# FR5969_BME280_v2_0_2.net
KiCad netlist of a schematic drawn in EAGLE
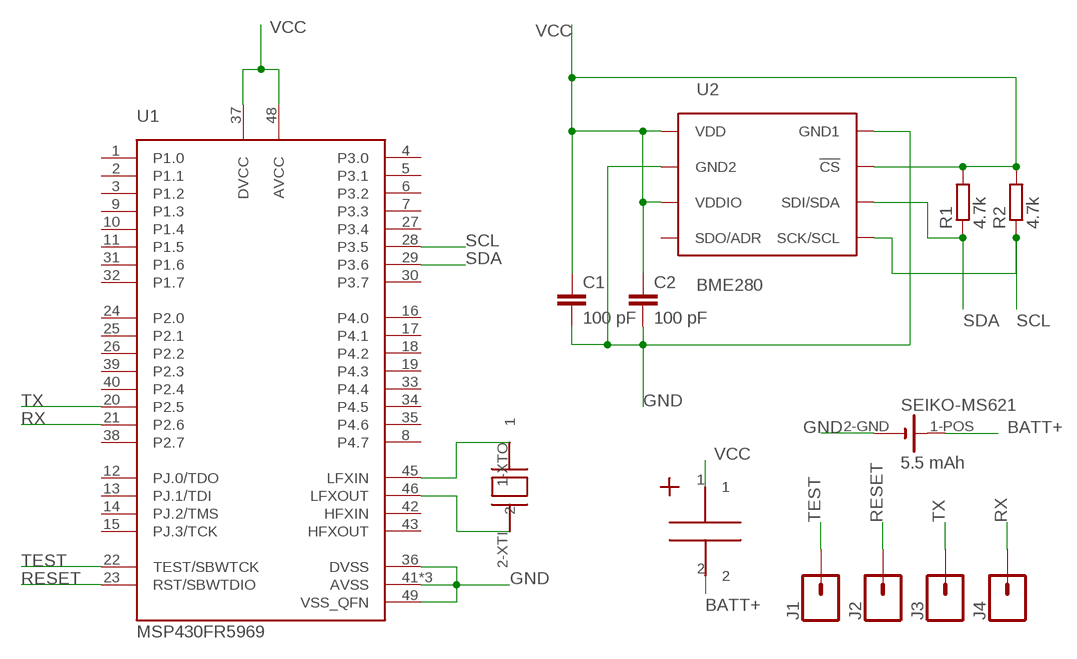
[diagram p0: schematic, sheet 1]

(export (version "E")
  (design (tool "Eeschema 10.0.6"))
  (components
    (comp (ref "C1")
      (value "100 pF")
      (footprint "eagle-import:C0201")
      (libsource (lib "eagle-import") (part "C-EUC0201"))
    )
    (comp (ref "C2")
      (value "100 pF")
      (footprint "eagle-import:C0201")
      (libsource (lib "eagle-import") (part "C-EUC0201"))
    )
    (comp (ref "J1")
      (value "CONN_01")
      (footprint "eagle-import:1X01")
      (libsource (lib "eagle-import") (part "CONN_01"))
    )
    (comp (ref "J2")
      (value "CONN_01")
      (footprint "eagle-import:1X01")
      (libsource (lib "eagle-import") (part "CONN_01"))
    )
    (comp (ref "J3")
      (value "CONN_01")
      (footprint "eagle-import:1X01")
      (libsource (lib "eagle-import") (part "CONN_01"))
    )
    (comp (ref "J4")
      (value "CONN_01")
      (footprint "eagle-import:1X01")
      (libsource (lib "eagle-import") (part "CONN_01"))
    )
    (comp (ref "R1")
      (value "4.7k")
      (footprint "eagle-import:R0201")
      (libsource (lib "eagle-import") (part "R-EU_R0201"))
    )
    (comp (ref "R2")
      (value "4.7k")
      (footprint "eagle-import:R0201")
      (libsource (lib "eagle-import") (part "R-EU_R0201"))
    )
    (comp (ref "SEIKO-MS621")
      (value "5.5 mAh")
      (footprint "eagle-import:SEIKO_MICRO")
      (libsource (lib "eagle-import") (part "SEIKO-MS621"))
    )
    (comp (ref "U$1")
      (value "CPX3225")
      (footprint "eagle-import:CPX3225_CHIP-CAP")
      (libsource (lib "eagle-import") (part "CPX3225"))
    )
    (comp (ref "U$2")
      (value "ABS06")
      (footprint "eagle-import:2.0X1.0RTC")
      (libsource (lib "eagle-import") (part "ABS06"))
    )
    (comp (ref "U1")
      (value "MSP430FR5969")
      (footprint "eagle-import:S-PVQFN-N48")
      (libsource (lib "eagle-import") (part "MSP430FR5969"))
    )
    (comp (ref "U2")
      (value "BME280")
      (footprint "eagle-import:BME280_LGA")
      (libsource (lib "eagle-import") (part "BME280"))
    )
  )
  (nets
    (net (code "1") (name "/BATT+") (class "Default")
      (node (ref "SEIKO-MS621") (pin "1-POS") (pinfunction "+_1-POS") (pintype "passive"))
      (node (ref "U$1") (pin "2") (pinfunction "2_2") (pintype "bidirectional"))
    )
    (net (code "2") (name "/GND") (class "Default")
      (node (ref "C1") (pin "2") (pinfunction "2_2") (pintype "passive"))
      (node (ref "C2") (pin "2") (pinfunction "2_2") (pintype "passive"))
      (node (ref "SEIKO-MS621") (pin "2-GND") (pinfunction "-_2-GND") (pintype "passive"))
      (node (ref "U1") (pin "36") (pinfunction "DVSS_36") (pintype "bidirectional"))
      (node (ref "U1") (pin "41") (pinfunction "AVSS_41") (pintype "bidirectional"))
      (node (ref "U1") (pin "44") (pinfunction "AVSS_44") (pintype "bidirectional"))
      (node (ref "U1") (pin "47") (pinfunction "AVSS_47") (pintype "bidirectional"))
      (node (ref "U1") (pin "49") (pinfunction "VSS_QFN_49") (pintype "bidirectional"))
      (node (ref "U2") (pin "P$1") (pinfunction "GND1_P$1") (pintype "bidirectional"))
      (node (ref "U2") (pin "P$7") (pinfunction "GND2_P$7") (pintype "bidirectional"))
    )
    (net (code "3") (name "/RESET") (class "Default")
      (node (ref "J2") (pin "1") (pinfunction "1_1") (pintype "passive"))
      (node (ref "U1") (pin "23") (pinfunction "RST/SBWTDIO_23") (pintype "bidirectional"))
    )
    (net (code "4") (name "/RX") (class "Default")
      (node (ref "J4") (pin "1") (pinfunction "1_1") (pintype "passive"))
      (node (ref "U1") (pin "21") (pinfunction "P2.6_21") (pintype "bidirectional"))
    )
    (net (code "5") (name "/SCL") (class "Default")
      (node (ref "R2") (pin "1") (pinfunction "1_1") (pintype "passive"))
      (node (ref "U1") (pin "28") (pinfunction "P3.5_28") (pintype "bidirectional"))
      (node (ref "U2") (pin "P$4") (pinfunction "SCK/SCL_P$4") (pintype "bidirectional"))
    )
    (net (code "6") (name "/SDA") (class "Default")
      (node (ref "R1") (pin "1") (pinfunction "1_1") (pintype "passive"))
      (node (ref "U1") (pin "29") (pinfunction "P3.6_29") (pintype "bidirectional"))
      (node (ref "U2") (pin "P$3") (pinfunction "SDI/SDA_P$3") (pintype "bidirectional"))
    )
    (net (code "7") (name "/TEST") (class "Default")
      (node (ref "J1") (pin "1") (pinfunction "1_1") (pintype "passive"))
      (node (ref "U1") (pin "22") (pinfunction "TEST/SBWTCK_22") (pintype "bidirectional"))
    )
    (net (code "8") (name "/TX") (class "Default")
      (node (ref "J3") (pin "1") (pinfunction "1_1") (pintype "passive"))
      (node (ref "U1") (pin "20") (pinfunction "P2.5_20") (pintype "bidirectional"))
    )
    (net (code "9") (name "/VCC") (class "Default")
      (node (ref "C1") (pin "1") (pinfunction "1_1") (pintype "passive"))
      (node (ref "C2") (pin "1") (pinfunction "1_1") (pintype "passive"))
      (node (ref "R1") (pin "2") (pinfunction "2_2") (pintype "passive"))
      (node (ref "R2") (pin "2") (pinfunction "2_2") (pintype "passive"))
      (node (ref "U$1") (pin "1") (pinfunction "1_1") (pintype "bidirectional"))
      (node (ref "U1") (pin "37") (pinfunction "DVCC_37") (pintype "bidirectional"))
      (node (ref "U1") (pin "48") (pinfunction "AVCC_48") (pintype "bidirectional"))
      (node (ref "U2") (pin "P$2") (pinfunction "~{CS}_P$2") (pintype "bidirectional"))
      (node (ref "U2") (pin "P$6") (pinfunction "VDDIO_P$6") (pintype "bidirectional"))
      (node (ref "U2") (pin "P$8") (pinfunction "VDD_P$8") (pintype "bidirectional"))
    )
    (net (code "10") (name "Net-(U$2-1)") (class "Default")
      (node (ref "U$2") (pin "1-XTO") (pinfunction "1_1-XTO") (pintype "bidirectional"))
      (node (ref "U1") (pin "45") (pinfunction "LFXIN_45") (pintype "bidirectional"))
    )
    (net (code "11") (name "Net-(U$2-2)") (class "Default")
      (node (ref "U$2") (pin "2-XTI") (pinfunction "2_2-XTI") (pintype "bidirectional"))
      (node (ref "U1") (pin "46") (pinfunction "LFXOUT_46") (pintype "bidirectional"))
    )
    (net (code "12") (name "unconnected-(U1-HFXIN-Pad42)") (class "Default")
      (node (ref "U1") (pin "42") (pinfunction "HFXIN_42") (pintype "bidirectional"))
    )
    (net (code "13") (name "unconnected-(U1-HFXOUT-Pad43)") (class "Default")
      (node (ref "U1") (pin "43") (pinfunction "HFXOUT_43") (pintype "bidirectional"))
    )
    (net (code "14") (name "unconnected-(U1-P1.0-Pad1)") (class "Default")
      (node (ref "U1") (pin "1") (pinfunction "P1.0_1") (pintype "bidirectional"))
    )
    (net (code "15") (name "unconnected-(U1-P1.1-Pad2)") (class "Default")
      (node (ref "U1") (pin "2") (pinfunction "P1.1_2") (pintype "bidirectional"))
    )
    (net (code "16") (name "unconnected-(U1-P1.2-Pad3)") (class "Default")
      (node (ref "U1") (pin "3") (pinfunction "P1.2_3") (pintype "bidirectional"))
    )
    (net (code "17") (name "unconnected-(U1-P1.3-Pad9)") (class "Default")
      (node (ref "U1") (pin "9") (pinfunction "P1.3_9") (pintype "bidirectional"))
    )
    (net (code "18") (name "unconnected-(U1-P1.4-Pad10)") (class "Default")
      (node (ref "U1") (pin "10") (pinfunction "P1.4_10") (pintype "bidirectional"))
    )
    (net (code "19") (name "unconnected-(U1-P1.5-Pad11)") (class "Default")
      (node (ref "U1") (pin "11") (pinfunction "P1.5_11") (pintype "bidirectional"))
    )
    (net (code "20") (name "unconnected-(U1-P1.6-Pad31)") (class "Default")
      (node (ref "U1") (pin "31") (pinfunction "P1.6_31") (pintype "bidirectional"))
    )
    (net (code "21") (name "unconnected-(U1-P1.7-Pad32)") (class "Default")
      (node (ref "U1") (pin "32") (pinfunction "P1.7_32") (pintype "bidirectional"))
    )
    (net (code "22") (name "unconnected-(U1-P2.0-Pad24)") (class "Default")
      (node (ref "U1") (pin "24") (pinfunction "P2.0_24") (pintype "bidirectional"))
    )
    (net (code "23") (name "unconnected-(U1-P2.1-Pad25)") (class "Default")
      (node (ref "U1") (pin "25") (pinfunction "P2.1_25") (pintype "bidirectional"))
    )
    (net (code "24") (name "unconnected-(U1-P2.2-Pad26)") (class "Default")
      (node (ref "U1") (pin "26") (pinfunction "P2.2_26") (pintype "bidirectional"))
    )
    (net (code "25") (name "unconnected-(U1-P2.3-Pad39)") (class "Default")
      (node (ref "U1") (pin "39") (pinfunction "P2.3_39") (pintype "bidirectional"))
    )
    (net (code "26") (name "unconnected-(U1-P2.4-Pad40)") (class "Default")
      (node (ref "U1") (pin "40") (pinfunction "P2.4_40") (pintype "bidirectional"))
    )
    (net (code "27") (name "unconnected-(U1-P2.7-Pad38)") (class "Default")
      (node (ref "U1") (pin "38") (pinfunction "P2.7_38") (pintype "bidirectional"))
    )
    (net (code "28") (name "unconnected-(U1-P3.0-Pad4)") (class "Default")
      (node (ref "U1") (pin "4") (pinfunction "P3.0_4") (pintype "bidirectional"))
    )
    (net (code "29") (name "unconnected-(U1-P3.1-Pad5)") (class "Default")
      (node (ref "U1") (pin "5") (pinfunction "P3.1_5") (pintype "bidirectional"))
    )
    (net (code "30") (name "unconnected-(U1-P3.2-Pad6)") (class "Default")
      (node (ref "U1") (pin "6") (pinfunction "P3.2_6") (pintype "bidirectional"))
    )
    (net (code "31") (name "unconnected-(U1-P3.3-Pad7)") (class "Default")
      (node (ref "U1") (pin "7") (pinfunction "P3.3_7") (pintype "bidirectional"))
    )
    (net (code "32") (name "unconnected-(U1-P3.4-Pad27)") (class "Default")
      (node (ref "U1") (pin "27") (pinfunction "P3.4_27") (pintype "bidirectional"))
    )
    (net (code "33") (name "unconnected-(U1-P3.7-Pad30)") (class "Default")
      (node (ref "U1") (pin "30") (pinfunction "P3.7_30") (pintype "bidirectional"))
    )
    (net (code "34") (name "unconnected-(U1-P4.0-Pad16)") (class "Default")
      (node (ref "U1") (pin "16") (pinfunction "P4.0_16") (pintype "bidirectional"))
    )
    (net (code "35") (name "unconnected-(U1-P4.1-Pad17)") (class "Default")
      (node (ref "U1") (pin "17") (pinfunction "P4.1_17") (pintype "bidirectional"))
    )
    (net (code "36") (name "unconnected-(U1-P4.2-Pad18)") (class "Default")
      (node (ref "U1") (pin "18") (pinfunction "P4.2_18") (pintype "bidirectional"))
    )
    (net (code "37") (name "unconnected-(U1-P4.3-Pad19)") (class "Default")
      (node (ref "U1") (pin "19") (pinfunction "P4.3_19") (pintype "bidirectional"))
    )
    (net (code "38") (name "unconnected-(U1-P4.4-Pad33)") (class "Default")
      (node (ref "U1") (pin "33") (pinfunction "P4.4_33") (pintype "bidirectional"))
    )
    (net (code "39") (name "unconnected-(U1-P4.5-Pad34)") (class "Default")
      (node (ref "U1") (pin "34") (pinfunction "P4.5_34") (pintype "bidirectional"))
    )
    (net (code "40") (name "unconnected-(U1-P4.6-Pad35)") (class "Default")
      (node (ref "U1") (pin "35") (pinfunction "P4.6_35") (pintype "bidirectional"))
    )
    (net (code "41") (name "unconnected-(U1-P4.7-Pad8)") (class "Default")
      (node (ref "U1") (pin "8") (pinfunction "P4.7_8") (pintype "bidirectional"))
    )
    (net (code "42") (name "unconnected-(U1-PJ.0{slash}TDO-Pad12)") (class "Default")
      (node (ref "U1") (pin "12") (pinfunction "PJ.0/TDO_12") (pintype "bidirectional"))
    )
    (net (code "43") (name "unconnected-(U1-PJ.1{slash}TDI-Pad13)") (class "Default")
      (node (ref "U1") (pin "13") (pinfunction "PJ.1/TDI_13") (pintype "bidirectional"))
    )
    (net (code "44") (name "unconnected-(U1-PJ.2{slash}TMS-Pad14)") (class "Default")
      (node (ref "U1") (pin "14") (pinfunction "PJ.2/TMS_14") (pintype "bidirectional"))
    )
    (net (code "45") (name "unconnected-(U1-PJ.3{slash}TCK-Pad15)") (class "Default")
      (node (ref "U1") (pin "15") (pinfunction "PJ.3/TCK_15") (pintype "bidirectional"))
    )
    (net (code "46") (name "unconnected-(U2-SDO{slash}ADR-PadP$5)") (class "Default")
      (node (ref "U2") (pin "P$5") (pinfunction "SDO/ADR_P$5") (pintype "bidirectional"))
    )
  )
)
